# PIC32MK.net
KiCad netlist of a schematic drawn in Altium Designer
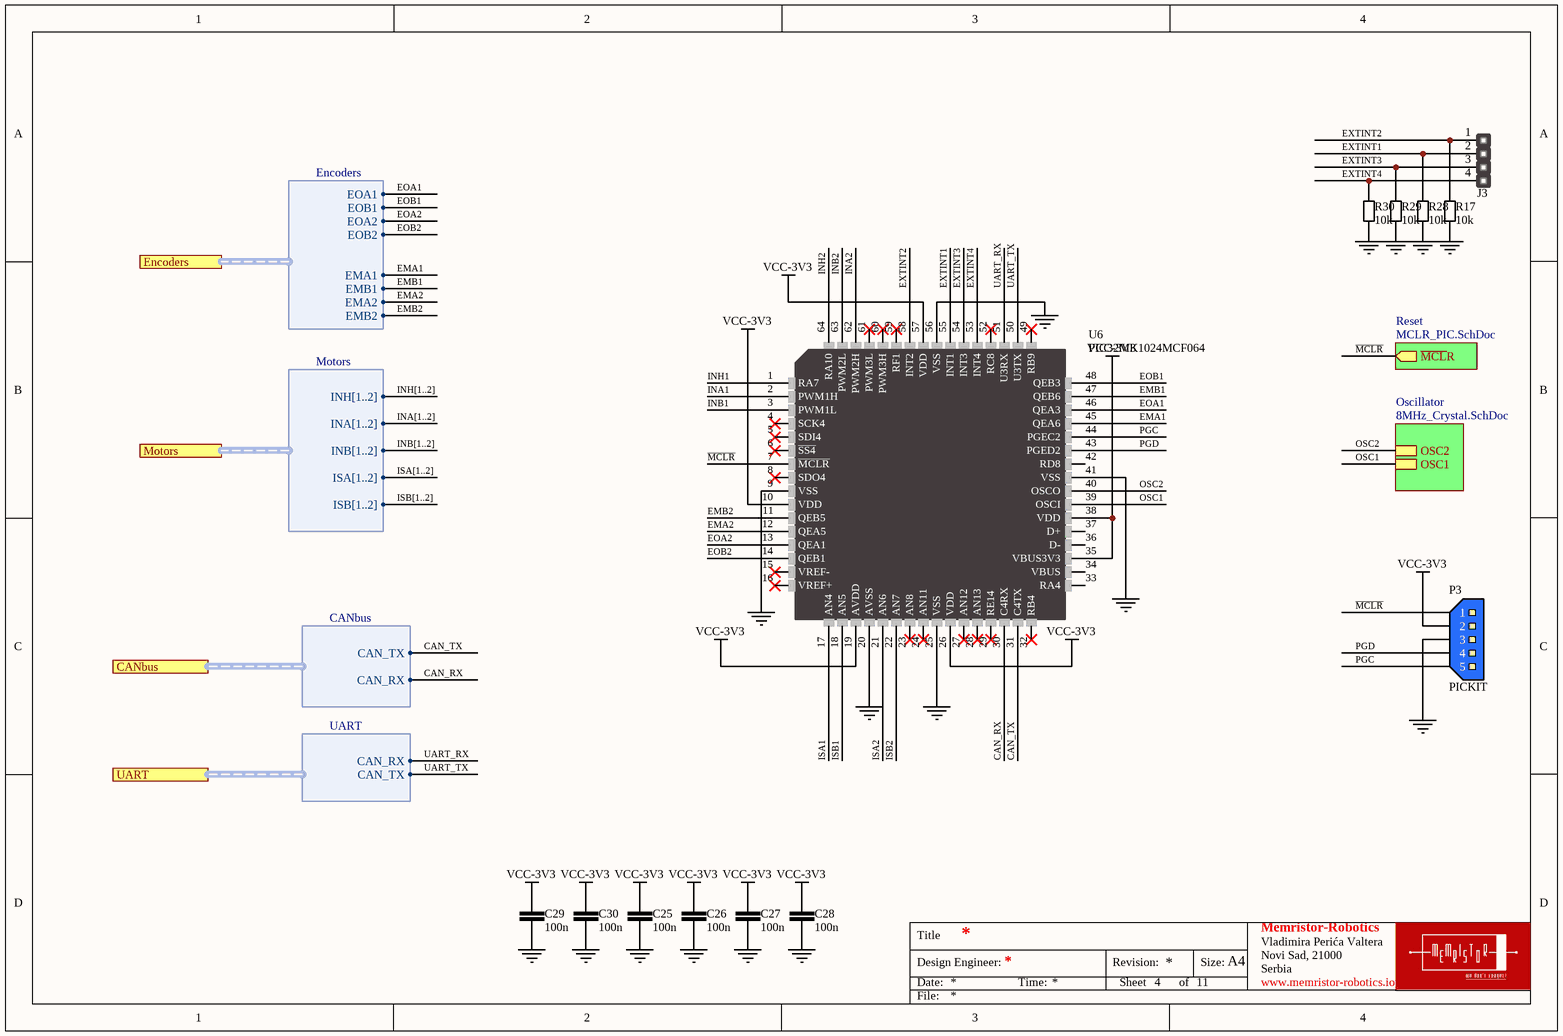
[diagram p0: PIC32MK.SchDoc]

(export (version "E")
  (design (tool "Eeschema 10.0.6"))
  (components
    (comp (ref "C25")
      (value "100n")
      (footprint "CER_0603")
      (description "CAP CER 100n 10V X5R 10% 0603")
      (libsource (lib "Capacitors") (part "06032105"))
    )
    (comp (ref "C26")
      (value "100n")
      (footprint "CER_0603")
      (description "CAP CER 100n 10V X5R 10% 0603")
      (libsource (lib "Capacitors") (part "06032105"))
    )
    (comp (ref "C27")
      (value "100n")
      (footprint "CER_0603")
      (description "CAP CER 100n 10V X5R 10% 0603")
      (libsource (lib "Capacitors") (part "06032105"))
    )
    (comp (ref "C28")
      (value "100n")
      (footprint "CER_0603")
      (description "CAP CER 100n 10V X5R 10% 0603")
      (libsource (lib "Capacitors") (part "06032105"))
    )
    (comp (ref "C29")
      (value "100n")
      (footprint "CER_0603")
      (description "CAP CER 100n 10V X5R 10% 0603")
      (libsource (lib "Capacitors") (part "06032105"))
    )
    (comp (ref "C30")
      (value "100n")
      (footprint "CER_0603")
      (description "CAP CER 100n 10V X5R 10% 0603")
      (libsource (lib "Capacitors") (part "06032105"))
    )
    (comp (ref "J3")
      (value "EXTINT")
      (footprint "HM1X4")
      (libsource (lib "Electro_Mechanical") (part "HEADER_1x4"))
    )
    (comp (ref "P3")
      (value "PICKIT")
      (footprint "TE CONNECTIVITY_5PIN_MALE")
      (description "BLUE_5PIN_CONECTOR")
      (fields (field (name "MANUFACTURER") "TE CONNECTIVITY / AMP"))
      (libsource (lib "Electro_Mechanical") (part "TE CONNECTIVITY_5PIN_MALE"))
    )
    (comp (ref "R17")
      (value "10k")
      (footprint "RESC2013X38N-0805-NOOVERLAY")
      (description "RES SMD 10 kOhm 1/8W 0805")
      (libsource (lib "Resistors") (part "000001002"))
    )
    (comp (ref "R28")
      (value "10k")
      (footprint "RESC2013X38N-0805-NOOVERLAY")
      (description "RES SMD 10 kOhm 1/8W 0805")
      (libsource (lib "Resistors") (part "000001002"))
    )
    (comp (ref "R29")
      (value "10k")
      (footprint "RESC2013X38N-0805-NOOVERLAY")
      (description "RES SMD 10 kOhm 1/8W 0805")
      (libsource (lib "Resistors") (part "000001002"))
    )
    (comp (ref "R30")
      (value "10k")
      (footprint "RESC2013X38N-0805-NOOVERLAY")
      (description "RES SMD 10 kOhm 1/8W 0805")
      (libsource (lib "Resistors") (part "000001002"))
    )
    (comp (ref "U6")
      (value "PIC32MK1024MCF064")
      (footprint "TQFP-64-500um")
      (description "IC MCU 32BIT 1MB FLASH 64TQFP")
      (libsource (lib "Integrated_circuits") (part "PIC32MK1024MCF064"))
    )
  )
  (nets
    (net (code "5") (name "/CAN_RX") (class "Default")
      (node (ref "U6") (pin "30") (pinfunction "C4RX_30") (pintype "passive"))
    )
    (net (code "6") (name "/CAN_TX") (class "Default")
      (node (ref "U6") (pin "31") (pinfunction "C4TX_31") (pintype "passive"))
    )
    (net (code "7") (name "/EMA1") (class "Default")
      (node (ref "U6") (pin "45") (pinfunction "QEA6_45") (pintype "passive"))
    )
    (net (code "8") (name "/EMA2") (class "Default")
      (node (ref "U6") (pin "12") (pinfunction "QEA5_12") (pintype "passive"))
    )
    (net (code "9") (name "/EMB1") (class "Default")
      (node (ref "U6") (pin "47") (pinfunction "QEB6_47") (pintype "passive"))
    )
    (net (code "10") (name "/EMB2") (class "Default")
      (node (ref "U6") (pin "11") (pinfunction "QEB5_11") (pintype "passive"))
    )
    (net (code "11") (name "/EOA1") (class "Default")
      (node (ref "U6") (pin "46") (pinfunction "QEA3_46") (pintype "passive"))
    )
    (net (code "12") (name "/EOA2") (class "Default")
      (node (ref "U6") (pin "13") (pinfunction "QEA1_13") (pintype "passive"))
    )
    (net (code "13") (name "/EOB1") (class "Default")
      (node (ref "U6") (pin "48") (pinfunction "QEB3_48") (pintype "passive"))
    )
    (net (code "14") (name "/EOB2") (class "Default")
      (node (ref "U6") (pin "14") (pinfunction "QEB1_14") (pintype "passive"))
    )
    (net (code "15") (name "/EXTINT1") (class "Default")
      (node (ref "J3") (pin "2") (pinfunction "1_2") (pintype "passive"))
      (node (ref "R28") (pin "2") (pinfunction "2_2") (pintype "passive"))
      (node (ref "U6") (pin "55") (pinfunction "INT1_55") (pintype "passive"))
    )
    (net (code "16") (name "/EXTINT2") (class "Default")
      (node (ref "J3") (pin "1") (pinfunction "1_1") (pintype "passive"))
      (node (ref "R17") (pin "2") (pinfunction "2_2") (pintype "passive"))
      (node (ref "U6") (pin "58") (pinfunction "INT2_58") (pintype "passive"))
    )
    (net (code "17") (name "/EXTINT3") (class "Default")
      (node (ref "J3") (pin "3") (pinfunction "1_3") (pintype "passive"))
      (node (ref "R29") (pin "2") (pinfunction "2_2") (pintype "passive"))
      (node (ref "U6") (pin "54") (pinfunction "INT3_54") (pintype "passive"))
    )
    (net (code "18") (name "/EXTINT4") (class "Default")
      (node (ref "J3") (pin "4") (pinfunction "4_4") (pintype "passive"))
      (node (ref "R30") (pin "2") (pinfunction "2_2") (pintype "passive"))
      (node (ref "U6") (pin "53") (pinfunction "INT4_53") (pintype "passive"))
    )
    (net (code "19") (name "/INA1") (class "Default")
      (node (ref "U6") (pin "2") (pinfunction "PWM1H_2") (pintype "passive"))
    )
    (net (code "20") (name "/INA2") (class "Default")
      (node (ref "U6") (pin "62") (pinfunction "PWM2H_62") (pintype "passive"))
    )
    (net (code "22") (name "/INB1") (class "Default")
      (node (ref "U6") (pin "3") (pinfunction "PWM1L_3") (pintype "passive"))
    )
    (net (code "23") (name "/INB2") (class "Default")
      (node (ref "U6") (pin "63") (pinfunction "PWM2L_63") (pintype "passive"))
    )
    (net (code "25") (name "/INH1") (class "Default")
      (node (ref "U6") (pin "1") (pinfunction "RA7_1") (pintype "passive"))
    )
    (net (code "26") (name "/INH2") (class "Default")
      (node (ref "U6") (pin "64") (pinfunction "RA10_64") (pintype "passive"))
    )
    (net (code "28") (name "/ISA1") (class "Default")
      (node (ref "U6") (pin "17") (pinfunction "AN4_17") (pintype "passive"))
    )
    (net (code "29") (name "/ISA2") (class "Default")
      (node (ref "U6") (pin "21") (pinfunction "AN6_21") (pintype "passive"))
    )
    (net (code "31") (name "/ISB1") (class "Default")
      (node (ref "U6") (pin "18") (pinfunction "AN5_18") (pintype "passive"))
    )
    (net (code "32") (name "/ISB2") (class "Default")
      (node (ref "U6") (pin "22") (pinfunction "AN7_22") (pintype "passive"))
    )
    (net (code "34") (name "/OSC1") (class "Default")
      (node (ref "U6") (pin "39") (pinfunction "OSCI_39") (pintype "passive"))
    )
    (net (code "35") (name "/OSC2") (class "Default")
      (node (ref "U6") (pin "40") (pinfunction "OSCO_40") (pintype "passive"))
    )
    (net (code "36") (name "/PGC") (class "Default")
      (node (ref "P3") (pin "5") (pinfunction "5_5") (pintype "passive"))
      (node (ref "U6") (pin "44") (pinfunction "PGEC2_44") (pintype "passive"))
    )
    (net (code "37") (name "/PGD") (class "Default")
      (node (ref "P3") (pin "4") (pinfunction "4_4") (pintype "passive"))
      (node (ref "U6") (pin "43") (pinfunction "PGED2_43") (pintype "passive"))
    )
    (net (code "38") (name "/UART_RX") (class "Default")
      (node (ref "U6") (pin "51") (pinfunction "U3RX_51") (pintype "passive"))
    )
    (net (code "39") (name "/UART_TX") (class "Default")
      (node (ref "U6") (pin "50") (pinfunction "U3TX_50") (pintype "passive"))
    )
    (net (code "44") (name "/~{MCLR}") (class "Default")
      (node (ref "P3") (pin "1") (pinfunction "1_1") (pintype "passive"))
      (node (ref "U6") (pin "7") (pinfunction "~{MCLR}_7") (pintype "passive"))
    )
    (net (code "45") (name "GND") (class "Default")
      (node (ref "C25") (pin "1") (pinfunction "1_1") (pintype "passive"))
      (node (ref "C26") (pin "1") (pinfunction "1_1") (pintype "passive"))
      (node (ref "C27") (pin "1") (pinfunction "1_1") (pintype "passive"))
      (node (ref "C28") (pin "1") (pinfunction "1_1") (pintype "passive"))
      (node (ref "C29") (pin "1") (pinfunction "1_1") (pintype "passive"))
      (node (ref "C30") (pin "1") (pinfunction "1_1") (pintype "passive"))
      (node (ref "P3") (pin "3") (pinfunction "3_3") (pintype "passive"))
      (node (ref "R17") (pin "1") (pinfunction "1_1") (pintype "passive"))
      (node (ref "R28") (pin "1") (pinfunction "1_1") (pintype "passive"))
      (node (ref "R29") (pin "1") (pinfunction "1_1") (pintype "passive"))
      (node (ref "R30") (pin "1") (pinfunction "1_1") (pintype "passive"))
      (node (ref "U6") (pin "20") (pinfunction "AVSS_20") (pintype "passive"))
      (node (ref "U6") (pin "25") (pinfunction "VSS_25") (pintype "passive"))
      (node (ref "U6") (pin "41") (pinfunction "VSS_41") (pintype "passive"))
      (node (ref "U6") (pin "56") (pinfunction "VSS_56") (pintype "passive"))
      (node (ref "U6") (pin "9") (pinfunction "VSS_9") (pintype "passive"))
    )
    (net (code "46") (name "VCC-3V3") (class "Default")
      (node (ref "C25") (pin "2") (pinfunction "2_2") (pintype "passive"))
      (node (ref "C26") (pin "2") (pinfunction "2_2") (pintype "passive"))
      (node (ref "C27") (pin "2") (pinfunction "2_2") (pintype "passive"))
      (node (ref "C28") (pin "2") (pinfunction "2_2") (pintype "passive"))
      (node (ref "C29") (pin "2") (pinfunction "2_2") (pintype "passive"))
      (node (ref "C30") (pin "2") (pinfunction "2_2") (pintype "passive"))
      (node (ref "P3") (pin "2") (pinfunction "2_2") (pintype "passive"))
      (node (ref "U6") (pin "10") (pinfunction "VDD_10") (pintype "passive"))
      (node (ref "U6") (pin "19") (pinfunction "AVDD_19") (pintype "passive"))
      (node (ref "U6") (pin "26") (pinfunction "VDD_26") (pintype "passive"))
      (node (ref "U6") (pin "35") (pinfunction "VBUS3V3_35") (pintype "passive"))
      (node (ref "U6") (pin "38") (pinfunction "VDD_38") (pintype "passive"))
      (node (ref "U6") (pin "57") (pinfunction "VDD_57") (pintype "passive"))
    )
    (net (code "47") (name "unconnected-(U6-AN8-Pad23)") (class "Default")
      (node (ref "U6") (pin "23") (pinfunction "AN8_23") (pintype "passive+no_connect"))
    )
    (net (code "48") (name "unconnected-(U6-AN11-Pad24)") (class "Default")
      (node (ref "U6") (pin "24") (pinfunction "AN11_24") (pintype "passive+no_connect"))
    )
    (net (code "49") (name "unconnected-(U6-AN12-Pad27)") (class "Default")
      (node (ref "U6") (pin "27") (pinfunction "AN12_27") (pintype "passive+no_connect"))
    )
    (net (code "50") (name "unconnected-(U6-AN13-Pad28)") (class "Default")
      (node (ref "U6") (pin "28") (pinfunction "AN13_28") (pintype "passive+no_connect"))
    )
    (net (code "51") (name "unconnected-(U6-D+-Pad37)") (class "Default")
      (node (ref "U6") (pin "37") (pinfunction "D+_37") (pintype "passive"))
    )
    (net (code "52") (name "unconnected-(U6-D--Pad36)") (class "Default")
      (node (ref "U6") (pin "36") (pinfunction "D-_36") (pintype "passive"))
    )
    (net (code "53") (name "unconnected-(U6-PWM3H-Pad60)") (class "Default")
      (node (ref "U6") (pin "60") (pinfunction "PWM3H_60") (pintype "passive+no_connect"))
    )
    (net (code "54") (name "unconnected-(U6-PWM3L-Pad61)") (class "Default")
      (node (ref "U6") (pin "61") (pinfunction "PWM3L_61") (pintype "passive+no_connect"))
    )
    (net (code "55") (name "unconnected-(U6-RA4-Pad33)") (class "Default")
      (node (ref "U6") (pin "33") (pinfunction "RA4_33") (pintype "passive"))
    )
    (net (code "56") (name "unconnected-(U6-RB4-Pad32)") (class "Default")
      (node (ref "U6") (pin "32") (pinfunction "RB4_32") (pintype "passive+no_connect"))
    )
    (net (code "57") (name "unconnected-(U6-RB9-Pad49)") (class "Default")
      (node (ref "U6") (pin "49") (pinfunction "RB9_49") (pintype "passive+no_connect"))
    )
    (net (code "58") (name "unconnected-(U6-RC8-Pad52)") (class "Default")
      (node (ref "U6") (pin "52") (pinfunction "RC8_52") (pintype "passive+no_connect"))
    )
    (net (code "59") (name "unconnected-(U6-RD8-Pad42)") (class "Default")
      (node (ref "U6") (pin "42") (pinfunction "RD8_42") (pintype "passive"))
    )
    (net (code "60") (name "unconnected-(U6-RE14-Pad29)") (class "Default")
      (node (ref "U6") (pin "29") (pinfunction "RE14_29") (pintype "passive+no_connect"))
    )
    (net (code "61") (name "unconnected-(U6-RF1-Pad59)") (class "Default")
      (node (ref "U6") (pin "59") (pinfunction "RF1_59") (pintype "passive+no_connect"))
    )
    (net (code "62") (name "unconnected-(U6-SCK4-Pad4)") (class "Default")
      (node (ref "U6") (pin "4") (pinfunction "SCK4_4") (pintype "passive+no_connect"))
    )
    (net (code "63") (name "unconnected-(U6-SDI4-Pad5)") (class "Default")
      (node (ref "U6") (pin "5") (pinfunction "SDI4_5") (pintype "passive+no_connect"))
    )
    (net (code "64") (name "unconnected-(U6-SDO4-Pad8)") (class "Default")
      (node (ref "U6") (pin "8") (pinfunction "SDO4_8") (pintype "passive+no_connect"))
    )
    (net (code "65") (name "unconnected-(U6-VBUS-Pad34)") (class "Default")
      (node (ref "U6") (pin "34") (pinfunction "VBUS_34") (pintype "passive"))
    )
    (net (code "66") (name "unconnected-(U6-VREF+-Pad16)") (class "Default")
      (node (ref "U6") (pin "16") (pinfunction "VREF+_16") (pintype "passive+no_connect"))
    )
    (net (code "67") (name "unconnected-(U6-VREF--Pad15)") (class "Default")
      (node (ref "U6") (pin "15") (pinfunction "VREF-_15") (pintype "passive+no_connect"))
    )
    (net (code "68") (name "unconnected-(U6-~{SS4}-Pad6)") (class "Default")
      (node (ref "U6") (pin "6") (pinfunction "~{SS4}_6") (pintype "passive+no_connect"))
    )
  )
)
